# main.net
KiCad netlist of a schematic drawn in Altium Designer
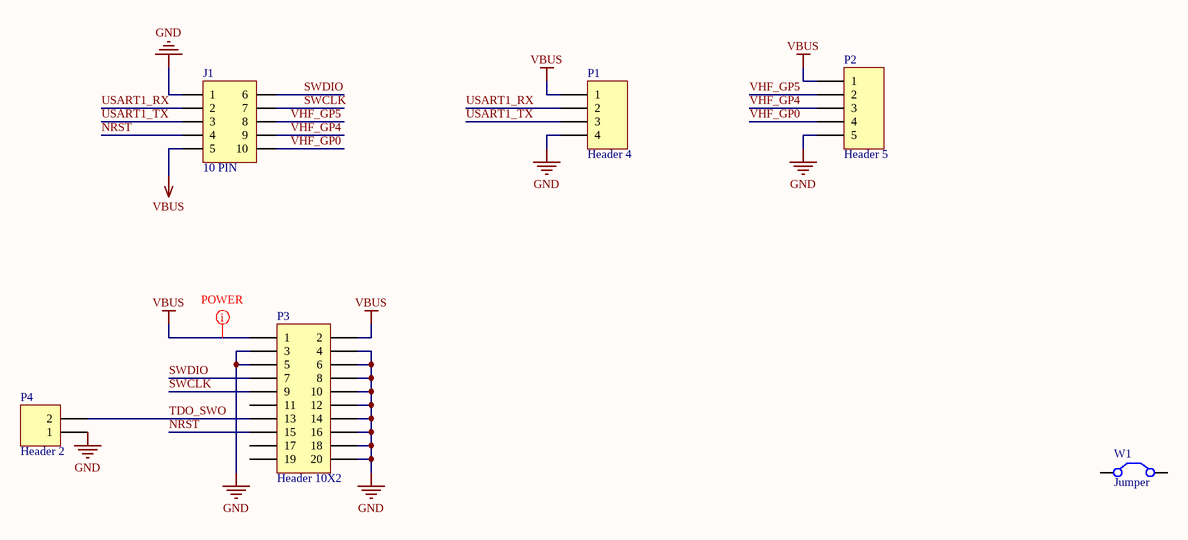
[diagram p0: main.SchDoc]

(export (version "E")
  (design (tool "Eeschema 10.0.6"))
  (components
    (comp (ref "J1")
      (value "10 PIN")
      (footprint "FTSH-105-01-F-D-K")
      (description "10 Pin Programming Header")
      (libsource (lib "lib-Connectors") (part "FTSH-105-01-F-D-K"))
    )
    (comp (ref "P1")
      (value "Header 4")
      (footprint "HDR1X4")
      (description "Header, 4-Pin")
      (fields (field (name "PUBLISHER") "Altium Limited"))
      (libsource (lib "Miscellaneous Connectors") (part "Header 4"))
    )
    (comp (ref "P2")
      (value "Header 5")
      (footprint "HDR1X5")
      (description "Header, 5-Pin")
      (fields (field (name "PUBLISHER") "Altium Limited"))
      (libsource (lib "Miscellaneous Connectors") (part "Header 5"))
    )
    (comp (ref "P3")
      (value "Header 10X2")
      (footprint "HDR2X10")
      (description "Header, 10-Pin, Dual row")
      (fields (field (name "PUBLISHER") "Altium Limited"))
      (libsource (lib "Miscellaneous Connectors") (part "Header 10X2"))
    )
    (comp (ref "P4")
      (value "Header 2")
      (footprint "HDR1X2")
      (description "Header, 2-Pin")
      (fields (field (name "PUBLISHER") "Altium Limited"))
      (libsource (lib "Miscellaneous Connectors") (part "Header 2"))
    )
    (comp (ref "W1")
      (value "Jumper")
      (footprint "RAD-0.2")
      (description "Jumper Wire")
      (fields (field (name "PUBLISHER") "Altium Limited"))
      (libsource (lib "Miscellaneous Devices") (part "Jumper"))
    )
  )
  (nets
    (net (code "1") (name "/NRST") (class "Default")
      (node (ref "J1") (pin "4") (pinfunction "4_4") (pintype "passive"))
      (node (ref "P3") (pin "15") (pinfunction "15_15") (pintype "passive"))
    )
    (net (code "2") (name "/SWCLK") (class "Default")
      (node (ref "J1") (pin "7") (pinfunction "7_7") (pintype "passive"))
      (node (ref "P3") (pin "9") (pinfunction "9_9") (pintype "passive"))
    )
    (net (code "3") (name "/SWDIO") (class "Default")
      (node (ref "J1") (pin "6") (pinfunction "6_6") (pintype "passive"))
      (node (ref "P3") (pin "7") (pinfunction "7_7") (pintype "passive"))
    )
    (net (code "4") (name "/TDO_SWO") (class "Default")
      (node (ref "P3") (pin "13") (pinfunction "13_13") (pintype "passive"))
      (node (ref "P4") (pin "2") (pinfunction "2_2") (pintype "passive"))
    )
    (net (code "5") (name "/USART1_RX") (class "Default")
      (node (ref "J1") (pin "2") (pinfunction "2_2") (pintype "passive"))
      (node (ref "P1") (pin "2") (pinfunction "2_2") (pintype "passive"))
    )
    (net (code "6") (name "/USART1_TX") (class "Default")
      (node (ref "J1") (pin "3") (pinfunction "3_3") (pintype "passive"))
      (node (ref "P1") (pin "3") (pinfunction "3_3") (pintype "passive"))
    )
    (net (code "7") (name "/VHF_GP0") (class "Default")
      (node (ref "J1") (pin "10") (pinfunction "10_10") (pintype "passive"))
      (node (ref "P2") (pin "4") (pinfunction "4_4") (pintype "passive"))
    )
    (net (code "8") (name "/VHF_GP4") (class "Default")
      (node (ref "J1") (pin "9") (pinfunction "9_9") (pintype "passive"))
      (node (ref "P2") (pin "3") (pinfunction "3_3") (pintype "passive"))
    )
    (net (code "9") (name "/VHF_GP5") (class "Default")
      (node (ref "J1") (pin "8") (pinfunction "8_8") (pintype "passive"))
      (node (ref "P2") (pin "2") (pinfunction "2_2") (pintype "passive"))
    )
    (net (code "10") (name "GND") (class "Default")
      (node (ref "J1") (pin "1") (pinfunction "1_1") (pintype "passive"))
      (node (ref "P1") (pin "4") (pinfunction "4_4") (pintype "passive"))
      (node (ref "P2") (pin "5") (pinfunction "5_5") (pintype "passive"))
      (node (ref "P3") (pin "10") (pinfunction "10_10") (pintype "passive"))
      (node (ref "P3") (pin "12") (pinfunction "12_12") (pintype "passive"))
      (node (ref "P3") (pin "14") (pinfunction "14_14") (pintype "passive"))
      (node (ref "P3") (pin "16") (pinfunction "16_16") (pintype "passive"))
      (node (ref "P3") (pin "18") (pinfunction "18_18") (pintype "passive"))
      (node (ref "P3") (pin "20") (pinfunction "20_20") (pintype "passive"))
      (node (ref "P3") (pin "3") (pinfunction "3_3") (pintype "passive"))
      (node (ref "P3") (pin "4") (pinfunction "4_4") (pintype "passive"))
      (node (ref "P3") (pin "5") (pinfunction "5_5") (pintype "passive"))
      (node (ref "P3") (pin "6") (pinfunction "6_6") (pintype "passive"))
      (node (ref "P3") (pin "8") (pinfunction "8_8") (pintype "passive"))
      (node (ref "P4") (pin "1") (pinfunction "1_1") (pintype "passive"))
    )
    (net (code "11") (name "VBUS") (class "Default")
      (node (ref "J1") (pin "5") (pinfunction "5_5") (pintype "passive"))
      (node (ref "P1") (pin "1") (pinfunction "1_1") (pintype "passive"))
      (node (ref "P2") (pin "1") (pinfunction "1_1") (pintype "passive"))
      (node (ref "P3") (pin "1") (pinfunction "1_1") (pintype "passive"))
      (node (ref "P3") (pin "2") (pinfunction "2_2") (pintype "passive"))
    )
    (net (code "12") (name "unconnected-(P3-Pad11)") (class "Default")
      (node (ref "P3") (pin "11") (pinfunction "11_11") (pintype "passive"))
    )
    (net (code "13") (name "unconnected-(P3-Pad17)") (class "Default")
      (node (ref "P3") (pin "17") (pinfunction "17_17") (pintype "passive"))
    )
    (net (code "14") (name "unconnected-(P3-Pad19)") (class "Default")
      (node (ref "P3") (pin "19") (pinfunction "19_19") (pintype "passive"))
    )
    (net (code "15") (name "unconnected-(W1-C1-Pad1)") (class "Default")
      (node (ref "W1") (pin "1") (pinfunction "C1_1") (pintype "passive"))
    )
    (net (code "16") (name "unconnected-(W1-C2-Pad2)") (class "Default")
      (node (ref "W1") (pin "2") (pinfunction "C2_2") (pintype "passive"))
    )
  )
)
